# Solar_Points.net
KiCad netlist of a schematic drawn in EAGLE
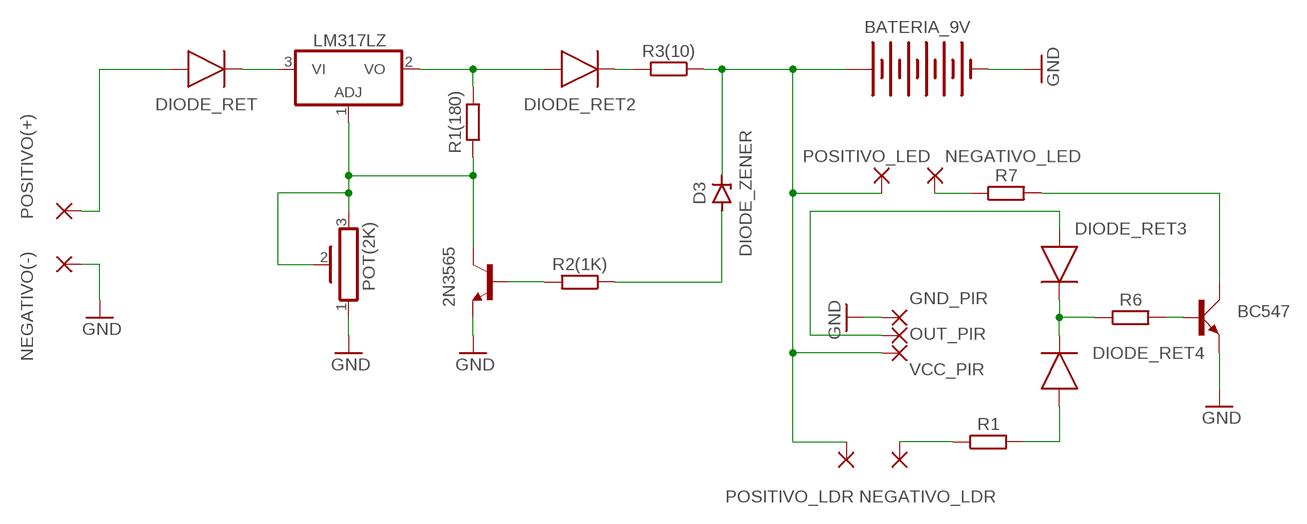
[diagram p0: schematic, sheet 1]

(export (version "E")
  (design (tool "Eeschema 10.0.6"))
  (components
    (comp (ref "2N3565")
      (value "2N3565")
      (footprint "eagle-import:TO92")
      (libsource (lib "eagle-import") (part "2N3565"))
    )
    (comp (ref "BATERIA_9V")
      (value "BATTERY-9VGENERIC")
      (footprint "eagle-import:BATTERY-GENERIC")
      (libsource (lib "eagle-import") (part "BATTERY-9VGENERIC"))
    )
    (comp (ref "BC547")
      (value "BC547")
      (footprint "eagle-import:SOT54A")
      (libsource (lib "eagle-import") (part "BC547"))
    )
    (comp (ref "D3")
      (value "DIODE_ZENER")
      (footprint "eagle-import:DIODE-AXIAL")
      (libsource (lib "eagle-import") (part "ZENER_DIODE-AXIAL"))
    )
    (comp (ref "DIODE_RET")
      (value "DIODEDIODE-AXIAL")
      (footprint "eagle-import:DIODE-AXIAL")
      (libsource (lib "eagle-import") (part "DIODEDIODE-AXIAL"))
    )
    (comp (ref "DIODE_RET2")
      (value "DIODEDIODE-AXIAL")
      (footprint "eagle-import:DIODE-AXIAL")
      (libsource (lib "eagle-import") (part "DIODEDIODE-AXIAL"))
    )
    (comp (ref "DIODE_RET3")
      (value "DIODEDIODE-AXIAL")
      (footprint "eagle-import:DIODE-AXIAL")
      (libsource (lib "eagle-import") (part "DIODEDIODE-AXIAL"))
    )
    (comp (ref "DIODE_RET4")
      (value "DIODEDIODE-AXIAL")
      (footprint "eagle-import:DIODE-AXIAL")
      (libsource (lib "eagle-import") (part "DIODEDIODE-AXIAL"))
    )
    (comp (ref "GND_PIR")
      (value "1,6/0,8")
      (footprint "eagle-import:1,6_0,8")
      (libsource (lib "eagle-import") (part "1,6/0,8"))
    )
    (comp (ref "LM317LZ")
      (value "LM317LZ")
      (footprint "eagle-import:TO92")
      (libsource (lib "eagle-import") (part "317LZLM"))
    )
    (comp (ref "NEGATIVO(-)")
      (value "3,81/1,4")
      (footprint "eagle-import:3,81_1,4")
      (libsource (lib "eagle-import") (part "3,81/1,4"))
    )
    (comp (ref "NEGATIVO_LDR")
      (value "1,6/0,8")
      (footprint "eagle-import:1,6_0,8")
      (libsource (lib "eagle-import") (part "1,6/0,8"))
    )
    (comp (ref "NEGATIVO_LED")
      (value "2,15/1,0")
      (footprint "eagle-import:2,15_1,0")
      (libsource (lib "eagle-import") (part "2,15/1,0"))
    )
    (comp (ref "OUT_PIR")
      (value "1,6/0,8")
      (footprint "eagle-import:1,6_0,8")
      (libsource (lib "eagle-import") (part "1,6/0,8"))
    )
    (comp (ref "POSITIVO(+)")
      (value "3,81/1,4")
      (footprint "eagle-import:3,81_1,4")
      (libsource (lib "eagle-import") (part "3,81/1,4"))
    )
    (comp (ref "POSITIVO_LDR")
      (value "1,6/0,8")
      (footprint "eagle-import:1,6_0,8")
      (libsource (lib "eagle-import") (part "1,6/0,8"))
    )
    (comp (ref "POSITIVO_LED")
      (value "2,15/1,0")
      (footprint "eagle-import:2,15_1,0")
      (libsource (lib "eagle-import") (part "2,15/1,0"))
    )
    (comp (ref "POT(2K)")
      (value "POT_HA-06")
      (footprint "eagle-import:HA-06-SM065")
      (libsource (lib "eagle-import") (part "POT_HA-06"))
    )
    (comp (ref "R1")
      (value "RESISTOR_AXIAL-10.16MM-PITCH")
      (footprint "eagle-import:RESAD1016W63L850D250B")
      (libsource (lib "eagle-import") (part "RESISTOR_AXIAL-10.16MM-PITCH"))
    )
    (comp (ref "R1(180)")
      (value "RESISTOR_AXIAL-10.16MM-PITCH")
      (footprint "eagle-import:RESAD1016W63L850D250B")
      (libsource (lib "eagle-import") (part "RESISTOR_AXIAL-10.16MM-PITCH"))
    )
    (comp (ref "R2(1K)")
      (value "RESISTOR_AXIAL-10.16MM-PITCH")
      (footprint "eagle-import:RESAD1016W63L850D250B")
      (libsource (lib "eagle-import") (part "RESISTOR_AXIAL-10.16MM-PITCH"))
    )
    (comp (ref "R3(10)")
      (value "RESISTOR_AXIAL-10.16MM-PITCH")
      (footprint "eagle-import:RESAD1016W63L850D250B")
      (libsource (lib "eagle-import") (part "RESISTOR_AXIAL-10.16MM-PITCH"))
    )
    (comp (ref "R6")
      (value "RESISTOR_AXIAL-10.16MM-PITCH")
      (footprint "eagle-import:RESAD1016W63L850D250B")
      (libsource (lib "eagle-import") (part "RESISTOR_AXIAL-10.16MM-PITCH"))
    )
    (comp (ref "R7")
      (value "RESISTOR_AXIAL-10.16MM-PITCH")
      (footprint "eagle-import:RESAD1016W63L850D250B")
      (libsource (lib "eagle-import") (part "RESISTOR_AXIAL-10.16MM-PITCH"))
    )
    (comp (ref "VCC_PIR")
      (value "1,6/0,8")
      (footprint "eagle-import:1,6_0,8")
      (libsource (lib "eagle-import") (part "1,6/0,8"))
    )
  )
  (nets
    (net (code "1") (name "GND") (class "Default")
      (node (ref "2N3565") (pin "3") (pinfunction "E_3") (pintype "passive"))
      (node (ref "BATERIA_9V") (pin "-") (pinfunction "-_-") (pintype "passive"))
      (node (ref "BC547") (pin "E") (pinfunction "E_E") (pintype "passive"))
      (node (ref "GND_PIR") (pin "1") (pinfunction "P_1") (pintype "passive"))
      (node (ref "NEGATIVO(-)") (pin "1") (pinfunction "P_1") (pintype "passive"))
      (node (ref "POT(2K)") (pin "1") (pinfunction "P$1_1") (pintype "passive"))
    )
    (net (code "2") (name "Net-(2N3565-B)") (class "Default")
      (node (ref "2N3565") (pin "2") (pinfunction "B_2") (pintype "passive"))
      (node (ref "R2(1K)") (pin "2") (pinfunction "2_2") (pintype "passive"))
    )
    (net (code "3") (name "Net-(2N3565-C)") (class "Default")
      (node (ref "2N3565") (pin "1") (pinfunction "C_1") (pintype "passive"))
      (node (ref "LM317LZ") (pin "1") (pinfunction "ADJ_1") (pintype "input"))
      (node (ref "POT(2K)") (pin "2") (pinfunction "P$2_2") (pintype "passive"))
      (node (ref "POT(2K)") (pin "3") (pinfunction "P$3_3") (pintype "passive"))
      (node (ref "R1(180)") (pin "1") (pinfunction "1_1") (pintype "passive"))
    )
    (net (code "4") (name "Net-(BC547-PadB)") (class "Default")
      (node (ref "BC547") (pin "B") (pinfunction "B_B") (pintype "passive"))
      (node (ref "R6") (pin "2") (pinfunction "2_2") (pintype "passive"))
    )
    (net (code "5") (name "Net-(BC547-PadC)") (class "Default")
      (node (ref "BC547") (pin "C") (pinfunction "C_C") (pintype "passive"))
      (node (ref "R7") (pin "2") (pinfunction "2_2") (pintype "passive"))
    )
    (net (code "6") (name "Net-(D3-A)") (class "Default")
      (node (ref "D3") (pin "1") (pinfunction "A_1") (pintype "passive"))
      (node (ref "R2(1K)") (pin "1") (pinfunction "1_1") (pintype "passive"))
    )
    (net (code "7") (name "Net-(D3-C)") (class "Default")
      (node (ref "BATERIA_9V") (pin "+") (pinfunction "+_+") (pintype "passive"))
      (node (ref "D3") (pin "2") (pinfunction "C_2") (pintype "passive"))
      (node (ref "POSITIVO_LDR") (pin "1") (pinfunction "P_1") (pintype "passive"))
      (node (ref "POSITIVO_LED") (pin "1") (pinfunction "P_1") (pintype "passive"))
      (node (ref "R3(10)") (pin "1") (pinfunction "1_1") (pintype "passive"))
      (node (ref "VCC_PIR") (pin "1") (pinfunction "P_1") (pintype "passive"))
    )
    (net (code "8") (name "Net-(DIODE_RET-A)") (class "Default")
      (node (ref "DIODE_RET") (pin "1") (pinfunction "A_1") (pintype "passive"))
      (node (ref "POSITIVO(+)") (pin "1") (pinfunction "P_1") (pintype "passive"))
    )
    (net (code "9") (name "Net-(DIODE_RET-C)") (class "Default")
      (node (ref "DIODE_RET") (pin "2") (pinfunction "C_2") (pintype "passive"))
      (node (ref "LM317LZ") (pin "3") (pinfunction "VI_3") (pintype "input"))
    )
    (net (code "10") (name "Net-(DIODE_RET2-A)") (class "Default")
      (node (ref "DIODE_RET2") (pin "1") (pinfunction "A_1") (pintype "passive"))
      (node (ref "LM317LZ") (pin "2") (pinfunction "VO_2") (pintype "passive"))
      (node (ref "R1(180)") (pin "2") (pinfunction "2_2") (pintype "passive"))
    )
    (net (code "11") (name "Net-(DIODE_RET2-C)") (class "Default")
      (node (ref "DIODE_RET2") (pin "2") (pinfunction "C_2") (pintype "passive"))
      (node (ref "R3(10)") (pin "2") (pinfunction "2_2") (pintype "passive"))
    )
    (net (code "12") (name "Net-(DIODE_RET3-A)") (class "Default")
      (node (ref "DIODE_RET3") (pin "1") (pinfunction "A_1") (pintype "passive"))
      (node (ref "OUT_PIR") (pin "1") (pinfunction "P_1") (pintype "passive"))
    )
    (net (code "13") (name "Net-(DIODE_RET3-C)") (class "Default")
      (node (ref "DIODE_RET3") (pin "2") (pinfunction "C_2") (pintype "passive"))
      (node (ref "DIODE_RET4") (pin "2") (pinfunction "C_2") (pintype "passive"))
      (node (ref "R6") (pin "1") (pinfunction "1_1") (pintype "passive"))
    )
    (net (code "14") (name "Net-(DIODE_RET4-A)") (class "Default")
      (node (ref "DIODE_RET4") (pin "1") (pinfunction "A_1") (pintype "passive"))
      (node (ref "R1") (pin "2") (pinfunction "2_2") (pintype "passive"))
    )
    (net (code "15") (name "Net-(NEGATIVO_LDR-P)") (class "Default")
      (node (ref "NEGATIVO_LDR") (pin "1") (pinfunction "P_1") (pintype "passive"))
      (node (ref "R1") (pin "1") (pinfunction "1_1") (pintype "passive"))
    )
    (net (code "16") (name "Net-(NEGATIVO_LED-P)") (class "Default")
      (node (ref "NEGATIVO_LED") (pin "1") (pinfunction "P_1") (pintype "passive"))
      (node (ref "R7") (pin "1") (pinfunction "1_1") (pintype "passive"))
    )
  )
)
